# FPGA_CONN_OUT.net
KiCad netlist of a schematic drawn in Altium Designer
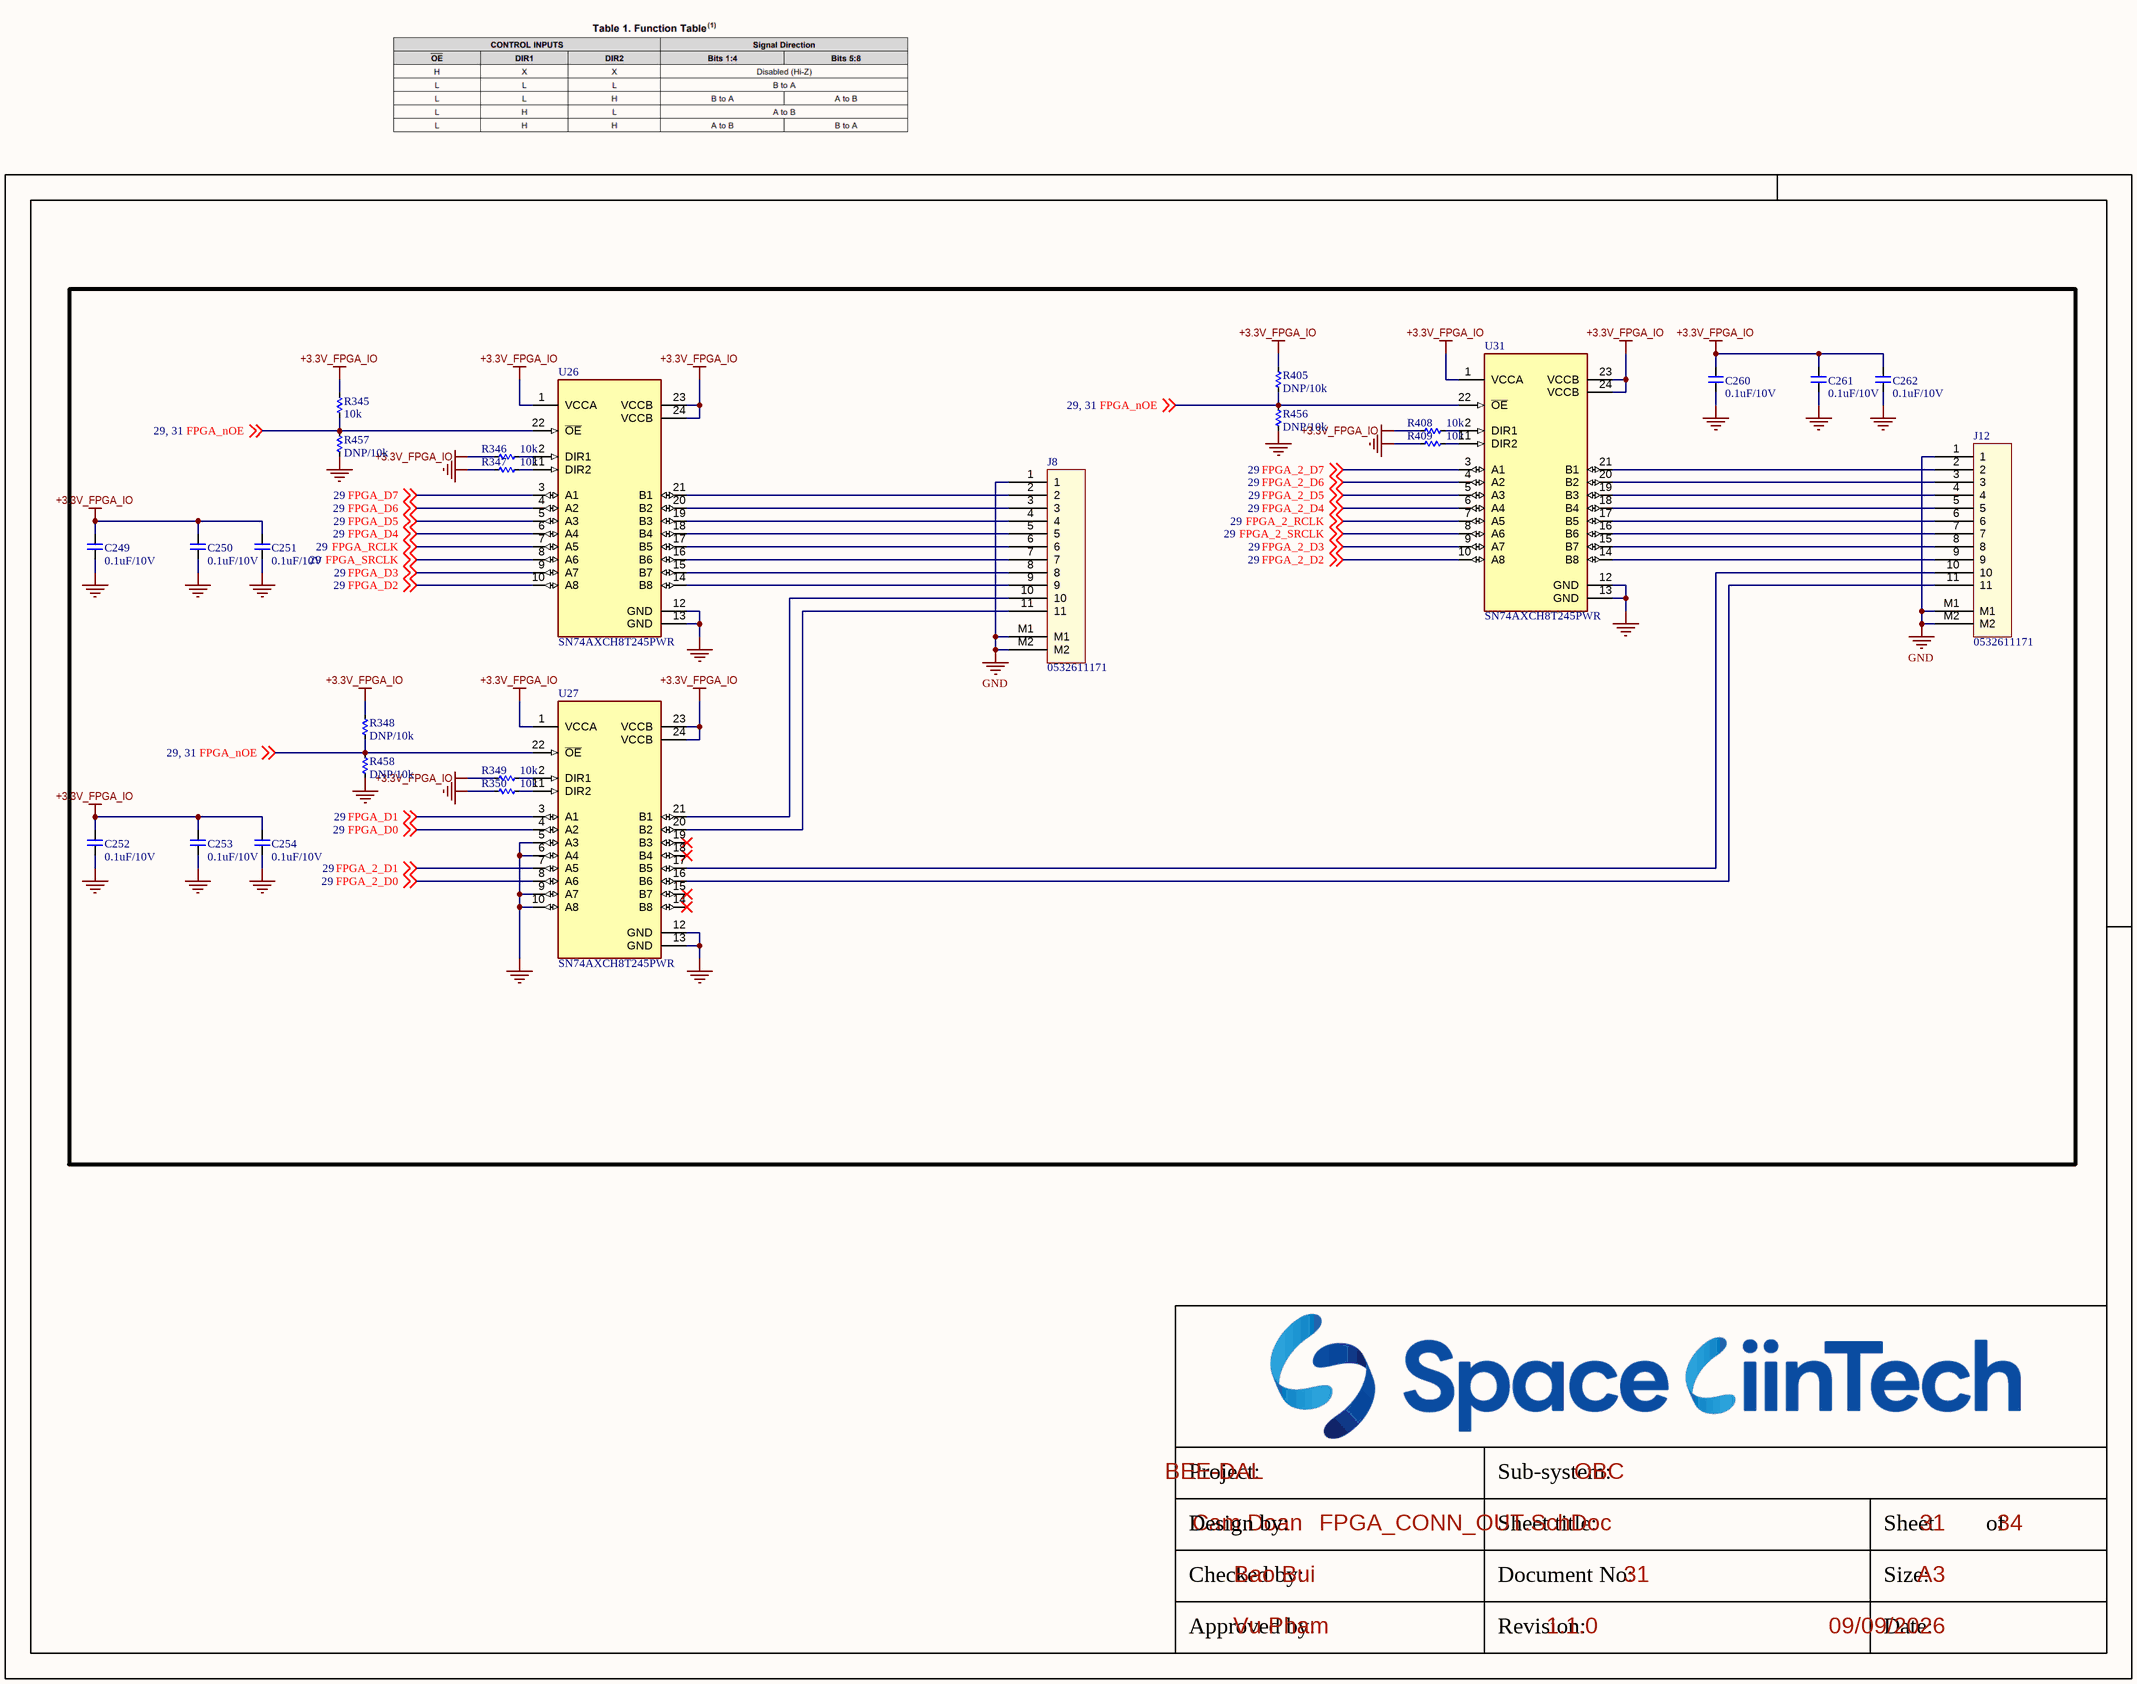
[diagram p0: FPGA_CONN_OUT.SchDoc]

(export (version "E")
  (design (tool "Eeschema 10.0.6"))
  (components
    (comp (ref "C249")
      (value "0.1uF/10V")
      (footprint "CAP_C_1005X50_L")
      (description "CAP")
      (libsource (lib "LABLIB") (part "_CAP_C_2"))
    )
    (comp (ref "C250")
      (value "0.1uF/10V")
      (footprint "CAP_C_1005X50_L")
      (description "CAP")
      (libsource (lib "LABLIB") (part "_CAP_C_2"))
    )
    (comp (ref "C251")
      (value "0.1uF/10V")
      (footprint "CAP_C_1005X50_L")
      (description "CAP")
      (libsource (lib "LABLIB") (part "_CAP_C_2"))
    )
    (comp (ref "C252")
      (value "0.1uF/10V")
      (footprint "CAP_C_1005X50_L")
      (description "CAP")
      (libsource (lib "LABLIB") (part "_CAP_C_2"))
    )
    (comp (ref "C253")
      (value "0.1uF/10V")
      (footprint "CAP_C_1005X50_L")
      (description "CAP")
      (libsource (lib "LABLIB") (part "_CAP_C_2"))
    )
    (comp (ref "C254")
      (value "0.1uF/10V")
      (footprint "CAP_C_1005X50_L")
      (description "CAP")
      (libsource (lib "LABLIB") (part "_CAP_C_2"))
    )
    (comp (ref "C260")
      (value "0.1uF/10V")
      (footprint "CAP_C_1005X50_L")
      (description "CAP")
      (libsource (lib "LABLIB") (part "_CAP_C_2"))
    )
    (comp (ref "C261")
      (value "0.1uF/10V")
      (footprint "CAP_C_1005X50_L")
      (description "CAP")
      (libsource (lib "LABLIB") (part "_CAP_C_2"))
    )
    (comp (ref "C262")
      (value "0.1uF/10V")
      (footprint "CAP_C_1005X50_L")
      (description "CAP")
      (libsource (lib "LABLIB") (part "_CAP_C_2"))
    )
    (comp (ref "J8")
      (value "0532611171")
      (footprint "MOLEX_0532611171")
      (libsource (lib "LABLIB") (part "Header 11x1_2M"))
    )
    (comp (ref "J12")
      (value "0532611171")
      (footprint "MOLEX_0532611171")
      (libsource (lib "LABLIB") (part "Header 11x1_2M"))
    )
    (comp (ref "R345")
      (value "10k")
      (footprint "RES_C_1005x30_L")
      (description "RES")
      (libsource (lib "LABLIB") (part "_RES_B_2"))
    )
    (comp (ref "R346")
      (value "10k")
      (footprint "RES_C_1005x30_L")
      (description "RES")
      (libsource (lib "LABLIB") (part "_RES_B_2"))
    )
    (comp (ref "R347")
      (value "10k")
      (footprint "RES_C_1005x30_L")
      (description "RES")
      (libsource (lib "LABLIB") (part "_RES_B_2"))
    )
    (comp (ref "R348")
      (value "DNP/10k")
      (footprint "RES_C_1005x30_L")
      (description "RES")
      (libsource (lib "LABLIB") (part "_RES_B_2"))
    )
    (comp (ref "R349")
      (value "10k")
      (footprint "RES_C_1005x30_L")
      (description "RES")
      (libsource (lib "LABLIB") (part "_RES_B_2"))
    )
    (comp (ref "R350")
      (value "10k")
      (footprint "RES_C_1005x30_L")
      (description "RES")
      (libsource (lib "LABLIB") (part "_RES_B_2"))
    )
    (comp (ref "R405")
      (value "DNP/10k")
      (footprint "RES_C_1005x30_L")
      (description "RES")
      (libsource (lib "LABLIB") (part "_RES_B_2"))
    )
    (comp (ref "R408")
      (value "10k")
      (footprint "RES_C_1005x30_L")
      (description "RES")
      (libsource (lib "LABLIB") (part "_RES_B_2"))
    )
    (comp (ref "R409")
      (value "10k")
      (footprint "RES_C_1005x30_L")
      (description "RES")
      (libsource (lib "LABLIB") (part "_RES_B_2"))
    )
    (comp (ref "R456")
      (value "DNP/10k")
      (footprint "RES_C_1005x30_L")
      (description "RES")
      (libsource (lib "LABLIB") (part "_RES_B_2"))
    )
    (comp (ref "R457")
      (value "DNP/10k")
      (footprint "RES_C_1005x30_L")
      (description "RES")
      (libsource (lib "LABLIB") (part "_RES_B_2"))
    )
    (comp (ref "R458")
      (value "DNP/10k")
      (footprint "RES_C_1005x30_L")
      (description "RES")
      (libsource (lib "LABLIB") (part "_RES_B_2"))
    )
    (comp (ref "U26")
      (value "SN74AXCH8T245PWR")
      (footprint "SOP65P640X120-24N")
      (description "8-Bit Dual-Supply Bus Transceiver")
      (fields (field (name "MF") "Texas Instruments"))
      (libsource (lib "LABLIB") (part "IC_voltage_level_SN74AXCH8T245PWR"))
    )
    (comp (ref "U27")
      (value "SN74AXCH8T245PWR")
      (footprint "SOP65P640X120-24N")
      (description "8-Bit Dual-Supply Bus Transceiver")
      (fields (field (name "MF") "Texas Instruments"))
      (libsource (lib "LABLIB") (part "IC_voltage_level_SN74AXCH8T245PWR"))
    )
    (comp (ref "U31")
      (value "SN74AXCH8T245PWR")
      (footprint "SOP65P640X120-24N")
      (description "8-Bit Dual-Supply Bus Transceiver")
      (fields (field (name "MF") "Texas Instruments"))
      (libsource (lib "LABLIB") (part "IC_voltage_level_SN74AXCH8T245PWR"))
    )
  )
  (nets
    (net (code "1") (name "+3.3V_FPGA_IO") (class "Default")
      (node (ref "C249") (pin "2") (pinfunction "2_2") (pintype "passive"))
      (node (ref "C250") (pin "2") (pinfunction "2_2") (pintype "passive"))
      (node (ref "C251") (pin "2") (pinfunction "2_2") (pintype "passive"))
      (node (ref "C252") (pin "2") (pinfunction "2_2") (pintype "passive"))
      (node (ref "C253") (pin "2") (pinfunction "2_2") (pintype "passive"))
      (node (ref "C254") (pin "2") (pinfunction "2_2") (pintype "passive"))
      (node (ref "C260") (pin "2") (pinfunction "2_2") (pintype "passive"))
      (node (ref "C261") (pin "2") (pinfunction "2_2") (pintype "passive"))
      (node (ref "C262") (pin "2") (pinfunction "2_2") (pintype "passive"))
      (node (ref "R345") (pin "1") (pinfunction "1_1") (pintype "passive"))
      (node (ref "R346") (pin "1") (pinfunction "1_1") (pintype "passive"))
      (node (ref "R348") (pin "1") (pinfunction "1_1") (pintype "passive"))
      (node (ref "R349") (pin "1") (pinfunction "1_1") (pintype "passive"))
      (node (ref "R405") (pin "1") (pinfunction "1_1") (pintype "passive"))
      (node (ref "R408") (pin "1") (pinfunction "1_1") (pintype "passive"))
      (node (ref "U26") (pin "1") (pinfunction "VCCA_1") (pintype "power_in"))
      (node (ref "U26") (pin "23") (pinfunction "VCCB_23") (pintype "power_in"))
      (node (ref "U26") (pin "24") (pinfunction "VCCB_24") (pintype "power_in"))
      (node (ref "U27") (pin "1") (pinfunction "VCCA_1") (pintype "power_in"))
      (node (ref "U27") (pin "23") (pinfunction "VCCB_23") (pintype "power_in"))
      (node (ref "U27") (pin "24") (pinfunction "VCCB_24") (pintype "power_in"))
      (node (ref "U31") (pin "1") (pinfunction "VCCA_1") (pintype "power_in"))
      (node (ref "U31") (pin "23") (pinfunction "VCCB_23") (pintype "power_in"))
      (node (ref "U31") (pin "24") (pinfunction "VCCB_24") (pintype "power_in"))
    )
    (net (code "2") (name "FPGA_2_D0") (class "Default")
      (node (ref "U27") (pin "8") (pinfunction "A6_8") (pintype "bidirectional"))
    )
    (net (code "3") (name "FPGA_2_D1") (class "Default")
      (node (ref "U27") (pin "7") (pinfunction "A5_7") (pintype "bidirectional"))
    )
    (net (code "4") (name "FPGA_2_D2") (class "Default")
      (node (ref "U31") (pin "10") (pinfunction "A8_10") (pintype "bidirectional"))
    )
    (net (code "5") (name "FPGA_2_D3") (class "Default")
      (node (ref "U31") (pin "9") (pinfunction "A7_9") (pintype "bidirectional"))
    )
    (net (code "6") (name "FPGA_2_D4") (class "Default")
      (node (ref "U31") (pin "6") (pinfunction "A4_6") (pintype "bidirectional"))
    )
    (net (code "7") (name "FPGA_2_D5") (class "Default")
      (node (ref "U31") (pin "5") (pinfunction "A3_5") (pintype "bidirectional"))
    )
    (net (code "8") (name "FPGA_2_D6") (class "Default")
      (node (ref "U31") (pin "4") (pinfunction "A2_4") (pintype "bidirectional"))
    )
    (net (code "9") (name "FPGA_2_D7") (class "Default")
      (node (ref "U31") (pin "3") (pinfunction "A1_3") (pintype "bidirectional"))
    )
    (net (code "10") (name "FPGA_2_RCLK") (class "Default")
      (node (ref "U31") (pin "7") (pinfunction "A5_7") (pintype "bidirectional"))
    )
    (net (code "11") (name "FPGA_2_SRCLK") (class "Default")
      (node (ref "U31") (pin "8") (pinfunction "A6_8") (pintype "bidirectional"))
    )
    (net (code "12") (name "FPGA_D0") (class "Default")
      (node (ref "U27") (pin "4") (pinfunction "A2_4") (pintype "bidirectional"))
    )
    (net (code "13") (name "FPGA_D1") (class "Default")
      (node (ref "U27") (pin "3") (pinfunction "A1_3") (pintype "bidirectional"))
    )
    (net (code "14") (name "FPGA_D2") (class "Default")
      (node (ref "U26") (pin "10") (pinfunction "A8_10") (pintype "bidirectional"))
    )
    (net (code "15") (name "FPGA_D3") (class "Default")
      (node (ref "U26") (pin "9") (pinfunction "A7_9") (pintype "bidirectional"))
    )
    (net (code "16") (name "FPGA_D4") (class "Default")
      (node (ref "U26") (pin "6") (pinfunction "A4_6") (pintype "bidirectional"))
    )
    (net (code "17") (name "FPGA_D5") (class "Default")
      (node (ref "U26") (pin "5") (pinfunction "A3_5") (pintype "bidirectional"))
    )
    (net (code "18") (name "FPGA_D6") (class "Default")
      (node (ref "U26") (pin "4") (pinfunction "A2_4") (pintype "bidirectional"))
    )
    (net (code "19") (name "FPGA_D7") (class "Default")
      (node (ref "U26") (pin "3") (pinfunction "A1_3") (pintype "bidirectional"))
    )
    (net (code "20") (name "FPGA_RCLK") (class "Default")
      (node (ref "U26") (pin "7") (pinfunction "A5_7") (pintype "bidirectional"))
    )
    (net (code "21") (name "FPGA_SRCLK") (class "Default")
      (node (ref "U26") (pin "8") (pinfunction "A6_8") (pintype "bidirectional"))
    )
    (net (code "22") (name "FPGA_nOE") (class "Default")
      (node (ref "R345") (pin "2") (pinfunction "2_2") (pintype "passive"))
      (node (ref "R348") (pin "2") (pinfunction "2_2") (pintype "passive"))
      (node (ref "R405") (pin "2") (pinfunction "2_2") (pintype "passive"))
      (node (ref "R456") (pin "1") (pinfunction "1_1") (pintype "passive"))
      (node (ref "R457") (pin "1") (pinfunction "1_1") (pintype "passive"))
      (node (ref "R458") (pin "1") (pinfunction "1_1") (pintype "passive"))
      (node (ref "U26") (pin "22") (pinfunction "~{OE}_22") (pintype "input"))
      (node (ref "U27") (pin "22") (pinfunction "~{OE}_22") (pintype "input"))
      (node (ref "U31") (pin "22") (pinfunction "~{OE}_22") (pintype "input"))
    )
    (net (code "23") (name "GND") (class "Default")
      (node (ref "C249") (pin "1") (pinfunction "1_1") (pintype "passive"))
      (node (ref "C250") (pin "1") (pinfunction "1_1") (pintype "passive"))
      (node (ref "C251") (pin "1") (pinfunction "1_1") (pintype "passive"))
      (node (ref "C252") (pin "1") (pinfunction "1_1") (pintype "passive"))
      (node (ref "C253") (pin "1") (pinfunction "1_1") (pintype "passive"))
      (node (ref "C254") (pin "1") (pinfunction "1_1") (pintype "passive"))
      (node (ref "C260") (pin "1") (pinfunction "1_1") (pintype "passive"))
      (node (ref "C261") (pin "1") (pinfunction "1_1") (pintype "passive"))
      (node (ref "C262") (pin "1") (pinfunction "1_1") (pintype "passive"))
      (node (ref "J12") (pin "1") (pinfunction "1_1") (pintype "passive"))
      (node (ref "J12") (pin "M1") (pinfunction "M1_M1") (pintype "passive"))
      (node (ref "J12") (pin "M2") (pinfunction "M2_M2") (pintype "passive"))
      (node (ref "J8") (pin "1") (pinfunction "1_1") (pintype "passive"))
      (node (ref "J8") (pin "M1") (pinfunction "M1_M1") (pintype "passive"))
      (node (ref "J8") (pin "M2") (pinfunction "M2_M2") (pintype "passive"))
      (node (ref "R347") (pin "1") (pinfunction "1_1") (pintype "passive"))
      (node (ref "R350") (pin "1") (pinfunction "1_1") (pintype "passive"))
      (node (ref "R409") (pin "1") (pinfunction "1_1") (pintype "passive"))
      (node (ref "R456") (pin "2") (pinfunction "2_2") (pintype "passive"))
      (node (ref "R457") (pin "2") (pinfunction "2_2") (pintype "passive"))
      (node (ref "R458") (pin "2") (pinfunction "2_2") (pintype "passive"))
      (node (ref "U26") (pin "12") (pinfunction "GND_12") (pintype "power_in"))
      (node (ref "U26") (pin "13") (pinfunction "GND_13") (pintype "power_in"))
      (node (ref "U27") (pin "10") (pinfunction "A8_10") (pintype "bidirectional"))
      (node (ref "U27") (pin "12") (pinfunction "GND_12") (pintype "power_in"))
      (node (ref "U27") (pin "13") (pinfunction "GND_13") (pintype "power_in"))
      (node (ref "U27") (pin "5") (pinfunction "A3_5") (pintype "bidirectional"))
      (node (ref "U27") (pin "6") (pinfunction "A4_6") (pintype "bidirectional"))
      (node (ref "U27") (pin "9") (pinfunction "A7_9") (pintype "bidirectional"))
      (node (ref "U31") (pin "12") (pinfunction "GND_12") (pintype "power_in"))
      (node (ref "U31") (pin "13") (pinfunction "GND_13") (pintype "power_in"))
    )
    (net (code "24") (name "Net-(U26-B1)") (class "Default")
      (node (ref "J8") (pin "2") (pinfunction "2_2") (pintype "passive"))
      (node (ref "U26") (pin "21") (pinfunction "B1_21") (pintype "bidirectional"))
    )
    (net (code "25") (name "Net-(U26-B2)") (class "Default")
      (node (ref "J8") (pin "3") (pinfunction "3_3") (pintype "passive"))
      (node (ref "U26") (pin "20") (pinfunction "B2_20") (pintype "bidirectional"))
    )
    (net (code "26") (name "Net-(U26-B3)") (class "Default")
      (node (ref "J8") (pin "4") (pinfunction "4_4") (pintype "passive"))
      (node (ref "U26") (pin "19") (pinfunction "B3_19") (pintype "bidirectional"))
    )
    (net (code "27") (name "Net-(U26-B4)") (class "Default")
      (node (ref "J8") (pin "5") (pinfunction "5_5") (pintype "passive"))
      (node (ref "U26") (pin "18") (pinfunction "B4_18") (pintype "bidirectional"))
    )
    (net (code "28") (name "Net-(U26-B5)") (class "Default")
      (node (ref "J8") (pin "6") (pinfunction "6_6") (pintype "passive"))
      (node (ref "U26") (pin "17") (pinfunction "B5_17") (pintype "bidirectional"))
    )
    (net (code "29") (name "Net-(U26-B6)") (class "Default")
      (node (ref "J8") (pin "7") (pinfunction "7_7") (pintype "passive"))
      (node (ref "U26") (pin "16") (pinfunction "B6_16") (pintype "bidirectional"))
    )
    (net (code "30") (name "Net-(U26-B7)") (class "Default")
      (node (ref "J8") (pin "8") (pinfunction "8_8") (pintype "passive"))
      (node (ref "U26") (pin "15") (pinfunction "B7_15") (pintype "bidirectional"))
    )
    (net (code "31") (name "Net-(U26-B8)") (class "Default")
      (node (ref "J8") (pin "9") (pinfunction "9_9") (pintype "passive"))
      (node (ref "U26") (pin "14") (pinfunction "B8_14") (pintype "bidirectional"))
    )
    (net (code "32") (name "Net-(U26-DIR1)") (class "Default")
      (node (ref "R346") (pin "2") (pinfunction "2_2") (pintype "passive"))
      (node (ref "U26") (pin "2") (pinfunction "DIR1_2") (pintype "input"))
    )
    (net (code "33") (name "Net-(U26-DIR2)") (class "Default")
      (node (ref "R347") (pin "2") (pinfunction "2_2") (pintype "passive"))
      (node (ref "U26") (pin "11") (pinfunction "DIR2_11") (pintype "input"))
    )
    (net (code "34") (name "Net-(U27-B1)") (class "Default")
      (node (ref "J8") (pin "10") (pinfunction "10_10") (pintype "passive"))
      (node (ref "U27") (pin "21") (pinfunction "B1_21") (pintype "bidirectional"))
    )
    (net (code "35") (name "Net-(U27-B2)") (class "Default")
      (node (ref "J8") (pin "11") (pinfunction "11_11") (pintype "passive"))
      (node (ref "U27") (pin "20") (pinfunction "B2_20") (pintype "bidirectional"))
    )
    (net (code "36") (name "Net-(U27-B5)") (class "Default")
      (node (ref "J12") (pin "10") (pinfunction "10_10") (pintype "passive"))
      (node (ref "U27") (pin "17") (pinfunction "B5_17") (pintype "bidirectional"))
    )
    (net (code "37") (name "Net-(U27-B6)") (class "Default")
      (node (ref "J12") (pin "11") (pinfunction "11_11") (pintype "passive"))
      (node (ref "U27") (pin "16") (pinfunction "B6_16") (pintype "bidirectional"))
    )
    (net (code "38") (name "Net-(U27-DIR1)") (class "Default")
      (node (ref "R349") (pin "2") (pinfunction "2_2") (pintype "passive"))
      (node (ref "U27") (pin "2") (pinfunction "DIR1_2") (pintype "input"))
    )
    (net (code "39") (name "Net-(U27-DIR2)") (class "Default")
      (node (ref "R350") (pin "2") (pinfunction "2_2") (pintype "passive"))
      (node (ref "U27") (pin "11") (pinfunction "DIR2_11") (pintype "input"))
    )
    (net (code "40") (name "Net-(U31-B1)") (class "Default")
      (node (ref "J12") (pin "2") (pinfunction "2_2") (pintype "passive"))
      (node (ref "U31") (pin "21") (pinfunction "B1_21") (pintype "bidirectional"))
    )
    (net (code "41") (name "Net-(U31-B2)") (class "Default")
      (node (ref "J12") (pin "3") (pinfunction "3_3") (pintype "passive"))
      (node (ref "U31") (pin "20") (pinfunction "B2_20") (pintype "bidirectional"))
    )
    (net (code "42") (name "Net-(U31-B3)") (class "Default")
      (node (ref "J12") (pin "4") (pinfunction "4_4") (pintype "passive"))
      (node (ref "U31") (pin "19") (pinfunction "B3_19") (pintype "bidirectional"))
    )
    (net (code "43") (name "Net-(U31-B4)") (class "Default")
      (node (ref "J12") (pin "5") (pinfunction "5_5") (pintype "passive"))
      (node (ref "U31") (pin "18") (pinfunction "B4_18") (pintype "bidirectional"))
    )
    (net (code "44") (name "Net-(U31-B5)") (class "Default")
      (node (ref "J12") (pin "6") (pinfunction "6_6") (pintype "passive"))
      (node (ref "U31") (pin "17") (pinfunction "B5_17") (pintype "bidirectional"))
    )
    (net (code "45") (name "Net-(U31-B6)") (class "Default")
      (node (ref "J12") (pin "7") (pinfunction "7_7") (pintype "passive"))
      (node (ref "U31") (pin "16") (pinfunction "B6_16") (pintype "bidirectional"))
    )
    (net (code "46") (name "Net-(U31-B7)") (class "Default")
      (node (ref "J12") (pin "8") (pinfunction "8_8") (pintype "passive"))
      (node (ref "U31") (pin "15") (pinfunction "B7_15") (pintype "bidirectional"))
    )
    (net (code "47") (name "Net-(U31-B8)") (class "Default")
      (node (ref "J12") (pin "9") (pinfunction "9_9") (pintype "passive"))
      (node (ref "U31") (pin "14") (pinfunction "B8_14") (pintype "bidirectional"))
    )
    (net (code "48") (name "Net-(U31-DIR1)") (class "Default")
      (node (ref "R408") (pin "2") (pinfunction "2_2") (pintype "passive"))
      (node (ref "U31") (pin "2") (pinfunction "DIR1_2") (pintype "input"))
    )
    (net (code "49") (name "Net-(U31-DIR2)") (class "Default")
      (node (ref "R409") (pin "2") (pinfunction "2_2") (pintype "passive"))
      (node (ref "U31") (pin "11") (pinfunction "DIR2_11") (pintype "input"))
    )
    (net (code "50") (name "unconnected-(U27-B3-Pad19)") (class "Default")
      (node (ref "U27") (pin "19") (pinfunction "B3_19") (pintype "bidirectional+no_connect"))
    )
    (net (code "51") (name "unconnected-(U27-B4-Pad18)") (class "Default")
      (node (ref "U27") (pin "18") (pinfunction "B4_18") (pintype "bidirectional+no_connect"))
    )
    (net (code "52") (name "unconnected-(U27-B7-Pad15)") (class "Default")
      (node (ref "U27") (pin "15") (pinfunction "B7_15") (pintype "bidirectional+no_connect"))
    )
    (net (code "53") (name "unconnected-(U27-B8-Pad14)") (class "Default")
      (node (ref "U27") (pin "14") (pinfunction "B8_14") (pintype "bidirectional+no_connect"))
    )
  )
)
